# thermokoppel.net
KiCad netlist of a schematic drawn in Altium Designer
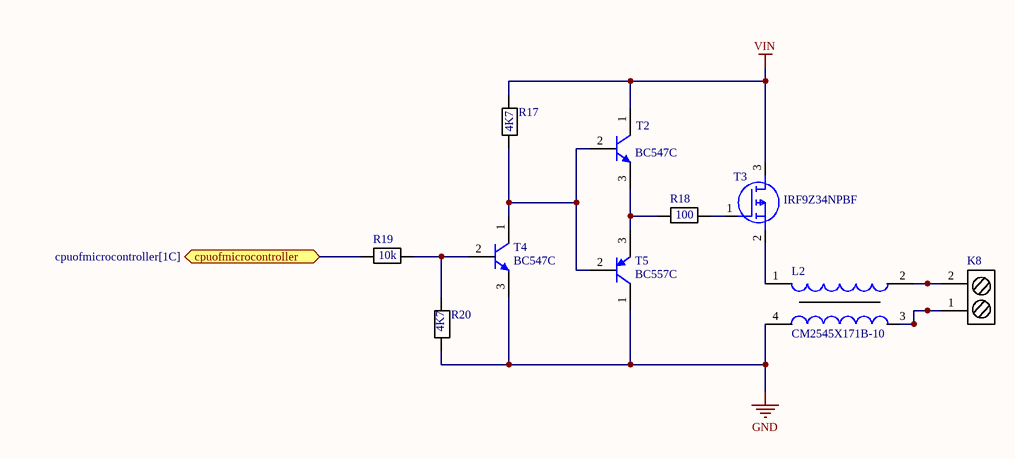
[diagram p0: thermokoppel.SchDoc]

(export (version "E")
  (design (tool "Eeschema 10.0.6"))
  (components
    (comp (ref "K8")
      (value "~")
      (footprint "printkroonsteen 2pin")
      (libsource (lib "Schlib1") (part "printkroonsteen 2pin"))
    )
    (comp (ref "L2")
      (value "CM2545X171B-10")
      (footprint "CM2545X171B10")
      (description "Transformer")
      (libsource (lib "Schlib1") (part "CM2545X171B-10"))
    )
    (comp (ref "R17")
      (value "4K7")
      (footprint "RESC2013X50X30LL20T20")
      (fields (field (name "MANUFACTURER") "Vishay Dale") (field (name "PART NUMBER") "CRCW08050000Z0EA"))
      (libsource (lib "Schlib1") (part "weerstand"))
    )
    (comp (ref "R18")
      (value "100")
      (footprint "RESC2013X50X30LL20T20")
      (fields (field (name "MANUFACTURER") "Vishay Dale") (field (name "PART NUMBER") "CRCW08050000Z0EA"))
      (libsource (lib "Schlib1") (part "weerstand"))
    )
    (comp (ref "R19")
      (value "10k")
      (footprint "RESC2013X50X30LL20T20")
      (fields (field (name "MANUFACTURER") "Vishay Dale") (field (name "PART NUMBER") "CRCW08050000Z0EA"))
      (libsource (lib "Schlib1") (part "weerstand"))
    )
    (comp (ref "R20")
      (value "4K7")
      (footprint "RESC2013X50X30LL20T20")
      (fields (field (name "MANUFACTURER") "Vishay Dale") (field (name "PART NUMBER") "CRCW08050000Z0EA"))
      (libsource (lib "Schlib1") (part "weerstand"))
    )
    (comp (ref "T2")
      (value "BC547C")
      (footprint "ONSC-TO-92-3-29-11")
      (description "Amplifier Transistor, NPN Silicon, 3-Pin TO-92, Bulk Box")
      (fields (field (name "MANUFACTURER") "On Semiconductor"))
      (libsource (lib "Schlib1") (part "BC547C"))
    )
    (comp (ref "T3")
      (value "IRF9Z34NPBF")
      (footprint "TO254P469X1042X1967-3P")
      (description "MOSFET (P-Channel)")
      (fields (field (name "MOUSER PART NUMBER") "942-IRF9Z34NPBF"))
      (libsource (lib "Schlib1") (part "IRF9Z34NPBF"))
    )
    (comp (ref "T4")
      (value "BC547C")
      (footprint "ONSC-TO-92-3-29-11")
      (description "Amplifier Transistor, NPN Silicon, 3-Pin TO-92, Bulk Box")
      (fields (field (name "MANUFACTURER") "On Semiconductor"))
      (libsource (lib "Schlib1") (part "BC547C"))
    )
    (comp (ref "T5")
      (value "BC557C")
      (footprint "ONSC-TO-92-3-29-11")
      (description "Amplifier Transistor, PNP Silicon, 3-Pin TO-92, Bulk Box")
      (fields (field (name "MANUFACTURER") "On Semiconductor"))
      (libsource (lib "Schlib1") (part "BC557C"))
    )
  )
  (nets
    (net (code "1") (name "/cpuofmicrocontroller") (class "Default")
      (node (ref "R19") (pin "1") (pinfunction "1_1") (pintype "passive"))
    )
    (net (code "2") (name "GND") (class "Default")
      (node (ref "L2") (pin "4") (pintype "passive"))
      (node (ref "R20") (pin "2") (pinfunction "2_2") (pintype "passive"))
      (node (ref "T4") (pin "3") (pinfunction "E_3") (pintype "passive"))
      (node (ref "T5") (pin "1") (pinfunction "C_1") (pintype "passive"))
    )
    (net (code "3") (name "Net-(K8-Pad1)") (class "Default")
      (node (ref "K8") (pin "1") (pintype "passive"))
      (node (ref "L2") (pin "3") (pintype "passive"))
    )
    (net (code "4") (name "Net-(K8-Pad2)") (class "Default")
      (node (ref "K8") (pin "2") (pintype "passive"))
      (node (ref "L2") (pin "2") (pintype "passive"))
    )
    (net (code "5") (name "Net-(T2-B)") (class "Default")
      (node (ref "R17") (pin "2") (pinfunction "2_2") (pintype "passive"))
      (node (ref "T2") (pin "2") (pinfunction "B_2") (pintype "passive"))
      (node (ref "T4") (pin "1") (pinfunction "C_1") (pintype "passive"))
      (node (ref "T5") (pin "2") (pinfunction "B_2") (pintype "passive"))
    )
    (net (code "6") (name "Net-(T2-E)") (class "Default")
      (node (ref "R18") (pin "1") (pinfunction "1_1") (pintype "passive"))
      (node (ref "T2") (pin "3") (pinfunction "E_3") (pintype "passive"))
      (node (ref "T5") (pin "3") (pinfunction "E_3") (pintype "passive"))
    )
    (net (code "7") (name "Net-(T3-G)") (class "Default")
      (node (ref "R18") (pin "2") (pinfunction "2_2") (pintype "passive"))
      (node (ref "T3") (pin "1") (pinfunction "G_1") (pintype "passive"))
    )
    (net (code "8") (name "Net-(T3-S)") (class "Default")
      (node (ref "L2") (pin "1") (pintype "passive"))
      (node (ref "T3") (pin "2") (pinfunction "S_2") (pintype "passive"))
    )
    (net (code "9") (name "Net-(T4-B)") (class "Default")
      (node (ref "R19") (pin "2") (pinfunction "2_2") (pintype "passive"))
      (node (ref "R20") (pin "1") (pinfunction "1_1") (pintype "passive"))
      (node (ref "T4") (pin "2") (pinfunction "B_2") (pintype "passive"))
    )
    (net (code "10") (name "VIN") (class "Default")
      (node (ref "R17") (pin "1") (pinfunction "1_1") (pintype "passive"))
      (node (ref "T2") (pin "1") (pinfunction "C_1") (pintype "passive"))
      (node (ref "T3") (pin "3") (pinfunction "D_3") (pintype "passive"))
    )
  )
)
